# mcu.net
KiCad netlist of a schematic drawn in Altium Designer
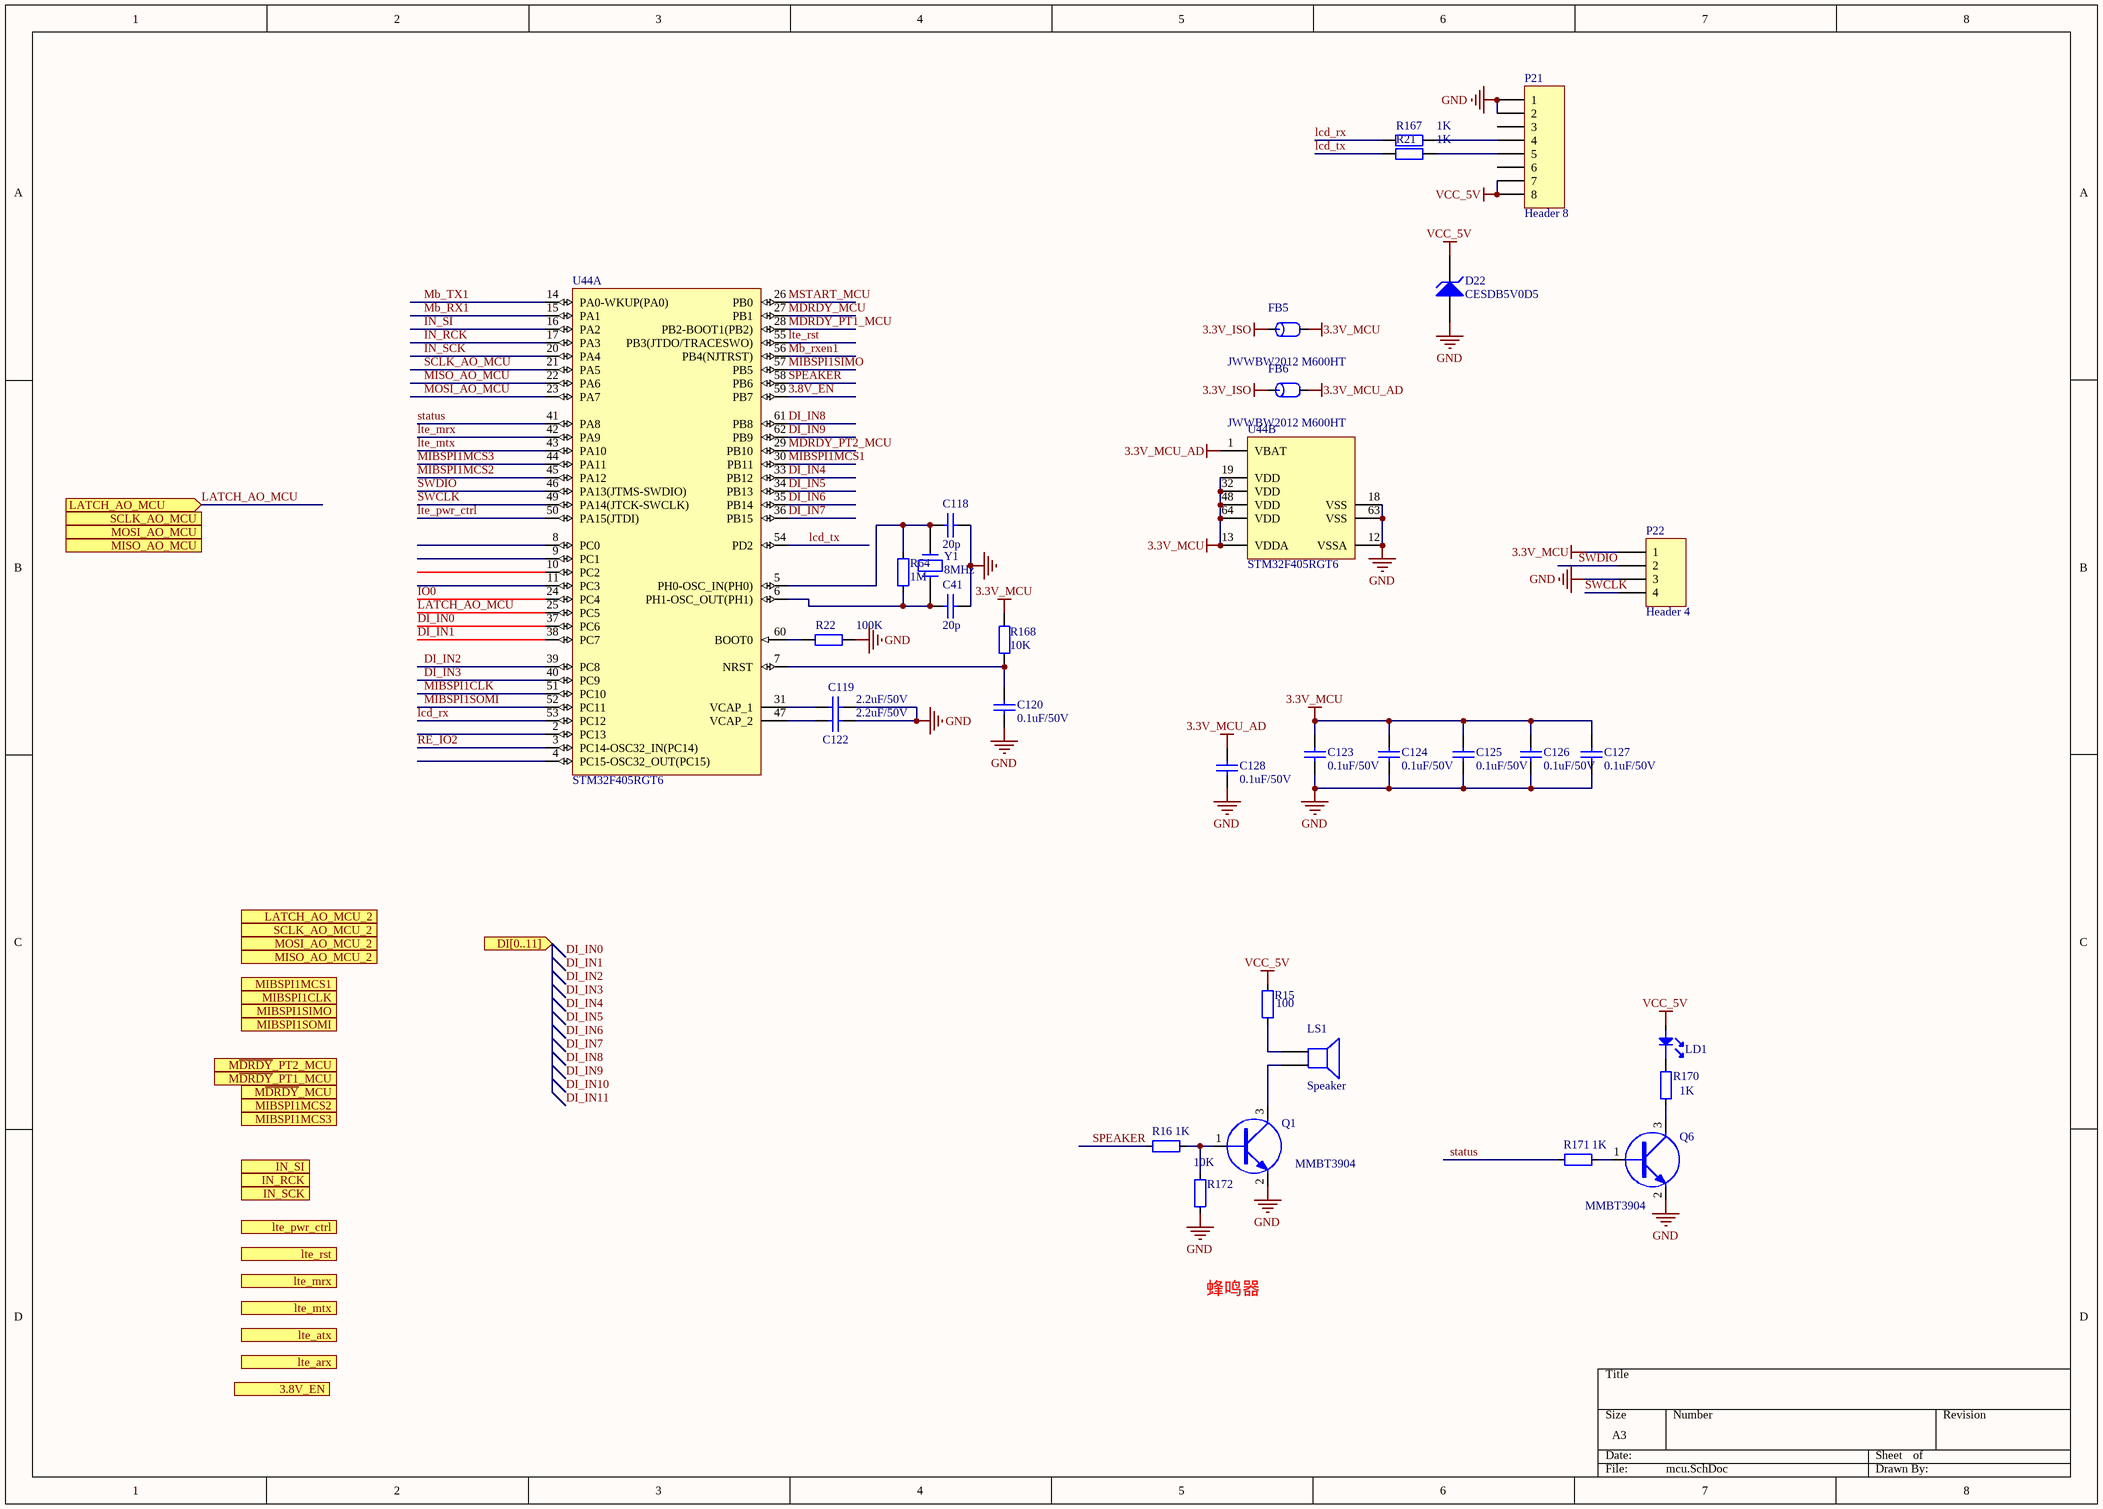
[diagram p0: mcu.SchDoc]

(export (version "E")
  (design (tool "Eeschema 10.0.6"))
  (components
    (comp (ref "C41")
      (value "20p")
      (footprint "0603c")
      (description "Capacitor")
      (libsource (lib "Schlib") (part "CAP"))
    )
    (comp (ref "C118")
      (value "20p")
      (footprint "0603c")
      (description "Capacitor")
      (libsource (lib "Schlib") (part "CAP"))
    )
    (comp (ref "C119")
      (value "2.2uF/50V")
      (footprint "0603C")
      (description "Capacitor")
      (fields (field (name "PUBLISHER") "Altium Limited"))
      (libsource (lib "Miscellaneous Devices") (part "Cap"))
    )
    (comp (ref "C120")
      (value "0.1uF/50V")
      (footprint "0603C")
      (description "Capacitor")
      (fields (field (name "PUBLISHER") "Altium Limited"))
      (libsource (lib "Miscellaneous Devices") (part "Cap"))
    )
    (comp (ref "C122")
      (value "2.2uF/50V")
      (footprint "0603C")
      (description "Capacitor")
      (fields (field (name "PUBLISHER") "Altium Limited"))
      (libsource (lib "Miscellaneous Devices") (part "Cap"))
    )
    (comp (ref "C123")
      (value "0.1uF/50V")
      (footprint "0603C")
      (description "Capacitor")
      (fields (field (name "PUBLISHER") "Altium Limited"))
      (libsource (lib "Miscellaneous Devices") (part "Cap"))
    )
    (comp (ref "C124")
      (value "0.1uF/50V")
      (footprint "0603C")
      (description "Capacitor")
      (fields (field (name "PUBLISHER") "Altium Limited"))
      (libsource (lib "Miscellaneous Devices") (part "Cap"))
    )
    (comp (ref "C125")
      (value "0.1uF/50V")
      (footprint "0603C")
      (description "Capacitor")
      (fields (field (name "PUBLISHER") "Altium Limited"))
      (libsource (lib "Miscellaneous Devices") (part "Cap"))
    )
    (comp (ref "C126")
      (value "0.1uF/50V")
      (footprint "0603C")
      (description "Capacitor")
      (fields (field (name "PUBLISHER") "Altium Limited"))
      (libsource (lib "Miscellaneous Devices") (part "Cap"))
    )
    (comp (ref "C127")
      (value "0.1uF/50V")
      (footprint "0603C")
      (description "Capacitor")
      (fields (field (name "PUBLISHER") "Altium Limited"))
      (libsource (lib "Miscellaneous Devices") (part "Cap"))
    )
    (comp (ref "C128")
      (value "0.1uF/50V")
      (footprint "0603C")
      (description "Capacitor")
      (fields (field (name "PUBLISHER") "Altium Limited"))
      (libsource (lib "Miscellaneous Devices") (part "Cap"))
    )
    (comp (ref "D22")
      (value "CESDB5V0D5")
      (footprint "sod323")
      (description "Zener Diode")
      (fields (field (name "PUBLISHER") "Altium Limited"))
      (libsource (lib "Miscellaneous Devices") (part "D Zener"))
    )
    (comp (ref "FB5")
      (value "JWWBW2012 M600HT")
      (footprint "0805R")
      (libsource (lib "Schlib_20110825") (part "FB"))
    )
    (comp (ref "FB6")
      (value "JWWBW2012 M600HT")
      (footprint "0805R")
      (libsource (lib "Schlib_20110825") (part "FB"))
    )
    (comp (ref "LD1")
      (value "LED_Green_19-217")
      (footprint "0603led")
      (libsource (lib "RC_M_D_00") (part "LED_Green_19-217"))
    )
    (comp (ref "LS1")
      (value "Speaker")
      (footprint "BUFFER_0905")
      (description "Loudspeaker")
      (fields (field (name "PUBLISHER") "Altium Limited"))
      (libsource (lib "Miscellaneous Devices") (part "Speaker"))
    )
    (comp (ref "P21")
      (value "Header 8")
      (footprint "2.0x8")
      (description "Header, 8-Pin")
      (fields (field (name "PUBLISHER") "Altium Limited"))
      (libsource (lib "Miscellaneous Connectors") (part "Header 8"))
    )
    (comp (ref "P22")
      (value "Header 4")
      (footprint "HDR1X4")
      (description "Header, 4-Pin")
      (fields (field (name "PUBLISHER") "Altium Limited"))
      (libsource (lib "Miscellaneous Connectors") (part "Header 4"))
    )
    (comp (ref "Q1")
      (value "MMBT3904")
      (footprint "SOT23-3")
      (libsource (lib "CenLib") (part "NPN_MMBT3904"))
    )
    (comp (ref "Q6")
      (value "MMBT3904")
      (footprint "SOT23-3")
      (libsource (lib "CenLib") (part "NPN_MMBT3904"))
    )
    (comp (ref "R15") (value "100") (footprint "0603R") (libsource (lib "RC_M_D_00") (part "RES0603")))
    (comp (ref "R16") (value "1K") (footprint "0603r") (libsource (lib "RC_M_D_00") (part "RES0603")))
    (comp (ref "R21") (value "1K") (footprint "0603R") (libsource (lib "MQlibrary") (part "Res0805M")))
    (comp (ref "R22") (value "100K") (footprint "0603R") (libsource (lib "MQlibrary") (part "Res0805M")))
    (comp (ref "R64") (value "1M") (footprint "0603R") (libsource (lib "RC_M_D_00") (part "RES0603")))
    (comp (ref "R167") (value "1K") (footprint "0603R") (libsource (lib "MQlibrary") (part "Res0805M")))
    (comp (ref "R168") (value "10K") (footprint "0603R") (libsource (lib "") (part "Res0805M_1")))
    (comp (ref "R170") (value "1K") (footprint "0603r") (libsource (lib "RC_M_D_00") (part "RES0603")))
    (comp (ref "R171") (value "1K") (footprint "0603r") (libsource (lib "RC_M_D_00") (part "RES0603")))
    (comp (ref "R172") (value "10K") (footprint "0603r") (libsource (lib "RC_M_D_00") (part "RES0603")))
    (comp (ref "U44")
      (value "STM32F405RGT6")
      (footprint "LQFP-64")
      (fields (field (name "MANUFACTURER") "STMicroelectronics"))
      (libsource (lib "STMicroelectronics STM32 F4") (part "STM32F405RGT6"))
    )
    (comp (ref "Y1")
      (value "8MHz")
      (footprint "CRAY_5032")
      (description "HC49S-8MHz")
      (libsource (lib "*") (part "CRYSTAL"))
    )
  )
  (nets
    (net (code "13") (name "/3.8V_EN") (class "Default")
      (node (ref "U44") (pin "59") (pinfunction "PB7_59") (pintype "bidirectional"))
    )
    (net (code "15") (name "/DI_IN0") (class "Default")
      (node (ref "U44") (pin "37") (pinfunction "PC6_37") (pintype "bidirectional"))
    )
    (net (code "16") (name "/DI_IN1") (class "Default")
      (node (ref "U44") (pin "38") (pinfunction "PC7_38") (pintype "bidirectional"))
    )
    (net (code "17") (name "/DI_IN2") (class "Default")
      (node (ref "U44") (pin "39") (pinfunction "PC8_39") (pintype "bidirectional"))
    )
    (net (code "18") (name "/DI_IN3") (class "Default")
      (node (ref "U44") (pin "40") (pinfunction "PC9_40") (pintype "bidirectional"))
    )
    (net (code "19") (name "/DI_IN4") (class "Default")
      (node (ref "U44") (pin "33") (pinfunction "PB12_33") (pintype "bidirectional"))
    )
    (net (code "20") (name "/DI_IN5") (class "Default")
      (node (ref "U44") (pin "34") (pinfunction "PB13_34") (pintype "bidirectional"))
    )
    (net (code "21") (name "/DI_IN6") (class "Default")
      (node (ref "U44") (pin "35") (pinfunction "PB14_35") (pintype "bidirectional"))
    )
    (net (code "22") (name "/DI_IN7") (class "Default")
      (node (ref "U44") (pin "36") (pinfunction "PB15_36") (pintype "bidirectional"))
    )
    (net (code "23") (name "/DI_IN8") (class "Default")
      (node (ref "U44") (pin "61") (pinfunction "PB8_61") (pintype "bidirectional"))
    )
    (net (code "24") (name "/DI_IN9") (class "Default")
      (node (ref "U44") (pin "62") (pinfunction "PB9_62") (pintype "bidirectional"))
    )
    (net (code "27") (name "/IN_RCK") (class "Default")
      (node (ref "U44") (pin "17") (pinfunction "PA3_17") (pintype "bidirectional"))
    )
    (net (code "28") (name "/IN_SCK") (class "Default")
      (node (ref "U44") (pin "20") (pinfunction "PA4_20") (pintype "bidirectional"))
    )
    (net (code "29") (name "/IN_SI") (class "Default")
      (node (ref "U44") (pin "16") (pinfunction "PA2_16") (pintype "bidirectional"))
    )
    (net (code "30") (name "/IO0") (class "Default")
      (node (ref "U44") (pin "24") (pinfunction "PC4_24") (pintype "bidirectional"))
    )
    (net (code "31") (name "/LATCH_AO_MCU") (class "Default")
      (node (ref "U44") (pin "25") (pinfunction "PC5_25") (pintype "bidirectional"))
    )
    (net (code "33") (name "/MIBSPI1CLK") (class "Default")
      (node (ref "U44") (pin "51") (pinfunction "PC10_51") (pintype "bidirectional"))
    )
    (net (code "34") (name "/MIBSPI1MCS1") (class "Default")
      (node (ref "U44") (pin "30") (pinfunction "PB11_30") (pintype "bidirectional"))
    )
    (net (code "35") (name "/MIBSPI1MCS2") (class "Default")
      (node (ref "U44") (pin "45") (pinfunction "PA12_45") (pintype "bidirectional"))
    )
    (net (code "36") (name "/MIBSPI1MCS3") (class "Default")
      (node (ref "U44") (pin "44") (pinfunction "PA11_44") (pintype "bidirectional"))
    )
    (net (code "37") (name "/MIBSPI1SIMO") (class "Default")
      (node (ref "U44") (pin "57") (pinfunction "PB5_57") (pintype "bidirectional"))
    )
    (net (code "38") (name "/MIBSPI1SOMI") (class "Default")
      (node (ref "U44") (pin "52") (pinfunction "PC11_52") (pintype "bidirectional"))
    )
    (net (code "39") (name "/MISO_AO_MCU") (class "Default")
      (node (ref "U44") (pin "22") (pinfunction "PA6_22") (pintype "bidirectional"))
    )
    (net (code "41") (name "/MOSI_AO_MCU") (class "Default")
      (node (ref "U44") (pin "23") (pinfunction "PA7_23") (pintype "bidirectional"))
    )
    (net (code "43") (name "/MSTART_MCU") (class "Default")
      (node (ref "U44") (pin "26") (pinfunction "PB0_26") (pintype "bidirectional"))
    )
    (net (code "44") (name "/Mb_RX1") (class "Default")
      (node (ref "U44") (pin "15") (pinfunction "PA1_15") (pintype "bidirectional"))
    )
    (net (code "45") (name "/Mb_TX1") (class "Default")
      (node (ref "U44") (pin "14") (pinfunction "PA0-WKUP(PA0)_14") (pintype "bidirectional"))
    )
    (net (code "46") (name "/Mb_rxen1") (class "Default")
      (node (ref "U44") (pin "56") (pinfunction "PB4(NJTRST)_56") (pintype "bidirectional"))
    )
    (net (code "47") (name "/M~{DRDY}_MCU") (class "Default")
      (node (ref "U44") (pin "27") (pinfunction "PB1_27") (pintype "bidirectional"))
    )
    (net (code "48") (name "/M~{DRDY}_PT1_MCU") (class "Default")
      (node (ref "U44") (pin "28") (pinfunction "PB2-BOOT1(PB2)_28") (pintype "bidirectional"))
    )
    (net (code "49") (name "/M~{DRDY}_PT2_MCU") (class "Default")
      (node (ref "U44") (pin "29") (pinfunction "PB10_29") (pintype "bidirectional"))
    )
    (net (code "50") (name "/RE_IO2") (class "Default")
      (node (ref "U44") (pin "3") (pinfunction "PC14-OSC32_IN(PC14)_3") (pintype "bidirectional"))
    )
    (net (code "51") (name "/SCLK_AO_MCU") (class "Default")
      (node (ref "U44") (pin "21") (pinfunction "PA5_21") (pintype "bidirectional"))
    )
    (net (code "53") (name "/SPEAKER") (class "Default")
      (node (ref "R16") (pin "2") (pinfunction "2_2") (pintype "passive"))
      (node (ref "U44") (pin "58") (pinfunction "PB6_58") (pintype "bidirectional"))
    )
    (net (code "54") (name "/SWCLK") (class "Default")
      (node (ref "P22") (pin "4") (pinfunction "4_4") (pintype "passive"))
      (node (ref "U44") (pin "49") (pinfunction "PA14(JTCK-SWCLK)_49") (pintype "bidirectional"))
    )
    (net (code "55") (name "/SWDIO") (class "Default")
      (node (ref "P22") (pin "2") (pinfunction "2_2") (pintype "passive"))
      (node (ref "U44") (pin "46") (pinfunction "PA13(JTMS-SWDIO)_46") (pintype "bidirectional"))
    )
    (net (code "56") (name "/lcd_rx") (class "Default")
      (node (ref "R167") (pin "1") (pinfunction "1_1") (pintype "passive"))
      (node (ref "U44") (pin "53") (pinfunction "PC12_53") (pintype "bidirectional"))
    )
    (net (code "57") (name "/lcd_tx") (class "Default")
      (node (ref "R21") (pin "1") (pinfunction "1_1") (pintype "passive"))
      (node (ref "U44") (pin "54") (pinfunction "PD2_54") (pintype "bidirectional"))
    )
    (net (code "60") (name "/lte_mrx") (class "Default")
      (node (ref "U44") (pin "42") (pinfunction "PA9_42") (pintype "bidirectional"))
    )
    (net (code "61") (name "/lte_mtx") (class "Default")
      (node (ref "U44") (pin "43") (pinfunction "PA10_43") (pintype "bidirectional"))
    )
    (net (code "62") (name "/lte_pwr_ctrl") (class "Default")
      (node (ref "U44") (pin "50") (pinfunction "PA15(JTDI)_50") (pintype "bidirectional"))
    )
    (net (code "63") (name "/lte_rst") (class "Default")
      (node (ref "U44") (pin "55") (pinfunction "PB3(JTDO/TRACESWO)_55") (pintype "bidirectional"))
    )
    (net (code "64") (name "/status") (class "Default")
      (node (ref "R171") (pin "1") (pinfunction "1_1") (pintype "passive"))
      (node (ref "U44") (pin "41") (pinfunction "PA8_41") (pintype "bidirectional"))
    )
    (net (code "65") (name "3.3V_ISO") (class "Default")
      (node (ref "FB5") (pin "1") (pintype "passive"))
      (node (ref "FB6") (pin "1") (pintype "passive"))
    )
    (net (code "66") (name "3.3V_MCU") (class "Default")
      (node (ref "C123") (pin "2") (pinfunction "2_2") (pintype "passive"))
      (node (ref "C124") (pin "2") (pinfunction "2_2") (pintype "passive"))
      (node (ref "C125") (pin "2") (pinfunction "2_2") (pintype "passive"))
      (node (ref "C126") (pin "2") (pinfunction "2_2") (pintype "passive"))
      (node (ref "C127") (pin "2") (pinfunction "2_2") (pintype "passive"))
      (node (ref "FB5") (pin "2") (pintype "passive"))
      (node (ref "P22") (pin "1") (pinfunction "1_1") (pintype "passive"))
      (node (ref "R168") (pin "2") (pinfunction "2_2") (pintype "passive"))
      (node (ref "U44") (pin "13") (pinfunction "VDDA_13") (pintype "power_in"))
      (node (ref "U44") (pin "19") (pinfunction "VDD_19") (pintype "power_in"))
      (node (ref "U44") (pin "32") (pinfunction "VDD_32") (pintype "power_in"))
      (node (ref "U44") (pin "48") (pinfunction "VDD_48") (pintype "power_in"))
      (node (ref "U44") (pin "64") (pinfunction "VDD_64") (pintype "power_in"))
    )
    (net (code "67") (name "3.3V_MCU_AD") (class "Default")
      (node (ref "C128") (pin "2") (pinfunction "2_2") (pintype "passive"))
      (node (ref "FB6") (pin "2") (pintype "passive"))
      (node (ref "U44") (pin "1") (pinfunction "VBAT_1") (pintype "power_in"))
    )
    (net (code "68") (name "GND") (class "Default")
      (node (ref "C118") (pin "1") (pinfunction "1_1") (pintype "passive"))
      (node (ref "C119") (pin "1") (pinfunction "1_1") (pintype "passive"))
      (node (ref "C120") (pin "1") (pinfunction "1_1") (pintype "passive"))
      (node (ref "C122") (pin "1") (pinfunction "1_1") (pintype "passive"))
      (node (ref "C123") (pin "1") (pinfunction "1_1") (pintype "passive"))
      (node (ref "C124") (pin "1") (pinfunction "1_1") (pintype "passive"))
      (node (ref "C125") (pin "1") (pinfunction "1_1") (pintype "passive"))
      (node (ref "C126") (pin "1") (pinfunction "1_1") (pintype "passive"))
      (node (ref "C127") (pin "1") (pinfunction "1_1") (pintype "passive"))
      (node (ref "C128") (pin "1") (pinfunction "1_1") (pintype "passive"))
      (node (ref "C41") (pin "1") (pinfunction "1_1") (pintype "passive"))
      (node (ref "D22") (pin "1") (pinfunction "A_1") (pintype "passive"))
      (node (ref "P21") (pin "1") (pinfunction "1_1") (pintype "passive"))
      (node (ref "P21") (pin "2") (pinfunction "2_2") (pintype "passive"))
      (node (ref "P22") (pin "3") (pinfunction "3_3") (pintype "passive"))
      (node (ref "Q1") (pin "2") (pinfunction "E_2") (pintype "passive"))
      (node (ref "Q6") (pin "2") (pinfunction "E_2") (pintype "passive"))
      (node (ref "R172") (pin "2") (pinfunction "2_2") (pintype "passive"))
      (node (ref "R22") (pin "2") (pinfunction "2_2") (pintype "passive"))
      (node (ref "U44") (pin "12") (pinfunction "VSSA_12") (pintype "power_in"))
      (node (ref "U44") (pin "18") (pinfunction "VSS_18") (pintype "power_in"))
      (node (ref "U44") (pin "63") (pinfunction "VSS_63") (pintype "power_in"))
    )
    (net (code "69") (name "Net-(LD1-Pad2)") (class "Default")
      (node (ref "LD1") (pin "2") (pinfunction "2_2") (pintype "passive"))
      (node (ref "R170") (pin "1") (pinfunction "1_1") (pintype "passive"))
    )
    (net (code "70") (name "Net-(LS1-Pad1)") (class "Default")
      (node (ref "LS1") (pin "1") (pinfunction "1_1") (pintype "passive"))
      (node (ref "R15") (pin "2") (pinfunction "2_2") (pintype "passive"))
    )
    (net (code "71") (name "Net-(P21-Pad4)") (class "Default")
      (node (ref "P21") (pin "4") (pinfunction "4_4") (pintype "passive"))
      (node (ref "R167") (pin "2") (pinfunction "2_2") (pintype "passive"))
    )
    (net (code "72") (name "Net-(P21-Pad5)") (class "Default")
      (node (ref "P21") (pin "5") (pinfunction "5_5") (pintype "passive"))
      (node (ref "R21") (pin "2") (pinfunction "2_2") (pintype "passive"))
    )
    (net (code "73") (name "Net-(Q1-B)") (class "Default")
      (node (ref "Q1") (pin "1") (pinfunction "B_1") (pintype "passive"))
      (node (ref "R16") (pin "1") (pinfunction "1_1") (pintype "passive"))
      (node (ref "R172") (pin "1") (pinfunction "1_1") (pintype "passive"))
    )
    (net (code "74") (name "Net-(Q1-C)") (class "Default")
      (node (ref "LS1") (pin "2") (pinfunction "2_2") (pintype "passive"))
      (node (ref "Q1") (pin "3") (pinfunction "C_3") (pintype "passive"))
    )
    (net (code "75") (name "Net-(Q6-B)") (class "Default")
      (node (ref "Q6") (pin "1") (pinfunction "B_1") (pintype "passive"))
      (node (ref "R171") (pin "2") (pinfunction "2_2") (pintype "passive"))
    )
    (net (code "76") (name "Net-(Q6-C)") (class "Default")
      (node (ref "Q6") (pin "3") (pinfunction "C_3") (pintype "passive"))
      (node (ref "R170") (pin "2") (pinfunction "2_2") (pintype "passive"))
    )
    (net (code "77") (name "Net-(U44A-BOOT0)") (class "Default")
      (node (ref "R22") (pin "1") (pinfunction "1_1") (pintype "passive"))
      (node (ref "U44") (pin "60") (pinfunction "BOOT0_60") (pintype "input"))
    )
    (net (code "78") (name "Net-(U44A-NRST)") (class "Default")
      (node (ref "C120") (pin "2") (pinfunction "2_2") (pintype "passive"))
      (node (ref "R168") (pin "1") (pinfunction "1_1") (pintype "passive"))
      (node (ref "U44") (pin "7") (pinfunction "NRST_7") (pintype "bidirectional"))
    )
    (net (code "79") (name "Net-(U44A-PH0-OSC_IN(PH0))") (class "Default")
      (node (ref "C118") (pin "2") (pinfunction "2_2") (pintype "passive"))
      (node (ref "R64") (pin "2") (pinfunction "2_2") (pintype "passive"))
      (node (ref "U44") (pin "5") (pinfunction "PH0-OSC_IN(PH0)_5") (pintype "bidirectional"))
      (node (ref "Y1") (pin "1") (pinfunction "1_1") (pintype "passive"))
    )
    (net (code "80") (name "Net-(U44A-PH1-OSC_OUT(PH1))") (class "Default")
      (node (ref "C41") (pin "2") (pinfunction "2_2") (pintype "passive"))
      (node (ref "R64") (pin "1") (pinfunction "1_1") (pintype "passive"))
      (node (ref "U44") (pin "6") (pinfunction "PH1-OSC_OUT(PH1)_6") (pintype "bidirectional"))
      (node (ref "Y1") (pin "2") (pinfunction "2_2") (pintype "passive"))
    )
    (net (code "81") (name "Net-(U44A-VCAP_1)") (class "Default")
      (node (ref "C119") (pin "2") (pinfunction "2_2") (pintype "passive"))
      (node (ref "U44") (pin "31") (pinfunction "VCAP_1_31") (pintype "power_in"))
    )
    (net (code "82") (name "Net-(U44A-VCAP_2)") (class "Default")
      (node (ref "C122") (pin "2") (pinfunction "2_2") (pintype "passive"))
      (node (ref "U44") (pin "47") (pinfunction "VCAP_2_47") (pintype "power_in"))
    )
    (net (code "83") (name "VCC_5V") (class "Default")
      (node (ref "D22") (pin "2") (pinfunction "K_2") (pintype "passive"))
      (node (ref "LD1") (pin "1") (pinfunction "1_1") (pintype "passive"))
      (node (ref "P21") (pin "7") (pinfunction "7_7") (pintype "passive"))
      (node (ref "P21") (pin "8") (pinfunction "8_8") (pintype "passive"))
      (node (ref "R15") (pin "1") (pinfunction "1_1") (pintype "passive"))
    )
    (net (code "84") (name "unconnected-(P21-Pad3)") (class "Default")
      (node (ref "P21") (pin "3") (pinfunction "3_3") (pintype "passive"))
    )
    (net (code "85") (name "unconnected-(P21-Pad6)") (class "Default")
      (node (ref "P21") (pin "6") (pinfunction "6_6") (pintype "passive"))
    )
    (net (code "86") (name "unconnected-(U44A-PC0-Pad8)") (class "Default")
      (node (ref "U44") (pin "8") (pinfunction "PC0_8") (pintype "bidirectional"))
    )
    (net (code "87") (name "unconnected-(U44A-PC1-Pad9)") (class "Default")
      (node (ref "U44") (pin "9") (pinfunction "PC1_9") (pintype "bidirectional"))
    )
    (net (code "88") (name "unconnected-(U44A-PC2-Pad10)") (class "Default")
      (node (ref "U44") (pin "10") (pinfunction "PC2_10") (pintype "bidirectional"))
    )
    (net (code "89") (name "unconnected-(U44A-PC3-Pad11)") (class "Default")
      (node (ref "U44") (pin "11") (pinfunction "PC3_11") (pintype "bidirectional"))
    )
    (net (code "90") (name "unconnected-(U44A-PC13-Pad2)") (class "Default")
      (node (ref "U44") (pin "2") (pinfunction "PC13_2") (pintype "bidirectional"))
    )
    (net (code "91") (name "unconnected-(U44A-PC15-OSC32_OUT(PC15)-Pad4)") (class "Default")
      (node (ref "U44") (pin "4") (pinfunction "PC15-OSC32_OUT(PC15)_4") (pintype "bidirectional"))
    )
  )
)
